# MixerModular_module.net
KiCad netlist of a schematic drawn in EAGLE
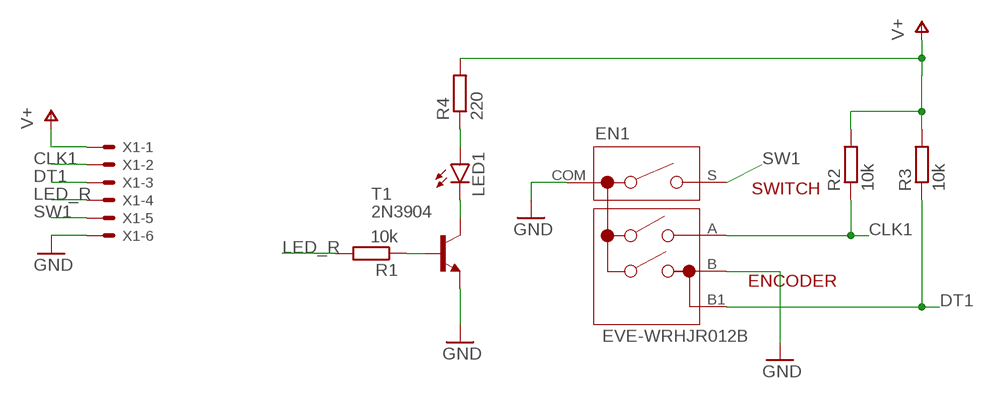
[diagram p0: schematic, sheet 1]

(export (version "E")
  (design (tool "Eeschema 10.0.6"))
  (components
    (comp (ref "EN1")
      (value "EVE-WRHJR012B")
      (footprint "eagle-import:EVE-WRHJR012B")
      (fields
        (field (name "DIGIKEY_PARTNO") "P15917-ND")
        (field (name "MANUFACTURER") "Panasonic Electronic Components")
        (field (name "CREATED_BY") "PCBLayout.com")
      )
      (libsource (lib "eagle-import") (part "EVE-WRHJR012B"))
    )
    (comp (ref "LED1")
      (value "LED5MM")
      (footprint "eagle-import:LED5MM")
      (libsource (lib "eagle-import") (part "LED5MM"))
    )
    (comp (ref "R1")
      (value "10k")
      (footprint "eagle-import:0207_10")
      (libsource (lib "eagle-import") (part "R-EU_0207/10"))
    )
    (comp (ref "R2")
      (value "10k")
      (footprint "eagle-import:0207_10")
      (libsource (lib "eagle-import") (part "R-EU_0207/10"))
    )
    (comp (ref "R3")
      (value "10k")
      (footprint "eagle-import:0207_10")
      (libsource (lib "eagle-import") (part "R-EU_0207/10"))
    )
    (comp (ref "R4")
      (value "220")
      (footprint "eagle-import:0207_10")
      (libsource (lib "eagle-import") (part "R-EU_0207/10"))
    )
    (comp (ref "T1")
      (value "2N3904")
      (footprint "eagle-import:TO92")
      (libsource (lib "eagle-import") (part "2N3904"))
    )
    (comp (ref "X1")
      (value "22-23-2061")
      (footprint "eagle-import:22-23-2061")
      (fields (field (name "MF") "MOLEX"))
      (libsource (lib "eagle-import") (part "22-23-2061"))
    )
  )
  (nets
    (net (code "1") (name "/CLK1") (class "Default")
      (node (ref "EN1") (pin "A") (pinfunction "A_A") (pintype "passive"))
      (node (ref "R2") (pin "1") (pinfunction "1_1") (pintype "passive"))
      (node (ref "X1") (pin "2") (pinfunction "S_2") (pintype "passive"))
    )
    (net (code "2") (name "/DT1") (class "Default")
      (node (ref "EN1") (pin "B1") (pinfunction "B1_B1") (pintype "passive"))
      (node (ref "R3") (pin "1") (pinfunction "1_1") (pintype "passive"))
      (node (ref "X1") (pin "3") (pinfunction "S_3") (pintype "passive"))
    )
    (net (code "3") (name "/LED_R") (class "Default")
      (node (ref "R1") (pin "2") (pinfunction "2_2") (pintype "passive"))
      (node (ref "X1") (pin "4") (pinfunction "S_4") (pintype "passive"))
    )
    (net (code "4") (name "/SW1") (class "Default")
      (node (ref "EN1") (pin "S") (pinfunction "S_S") (pintype "passive"))
      (node (ref "X1") (pin "5") (pinfunction "S_5") (pintype "passive"))
    )
    (net (code "5") (name "GND") (class "Default")
      (node (ref "EN1") (pin "B") (pinfunction "B_B") (pintype "passive"))
      (node (ref "EN1") (pin "COM") (pinfunction "COM_COM") (pintype "passive"))
      (node (ref "T1") (pin "3") (pinfunction "E_3") (pintype "passive"))
      (node (ref "X1") (pin "6") (pinfunction "S_6") (pintype "passive"))
    )
    (net (code "6") (name "Net-(LED1-C)") (class "Default")
      (node (ref "LED1") (pin "K") (pinfunction "C_K") (pintype "passive"))
      (node (ref "T1") (pin "1") (pinfunction "C_1") (pintype "passive"))
    )
    (net (code "7") (name "Net-(LED1-PadA)") (class "Default")
      (node (ref "LED1") (pin "A") (pinfunction "A_A") (pintype "passive"))
      (node (ref "R4") (pin "1") (pinfunction "1_1") (pintype "passive"))
    )
    (net (code "8") (name "Net-(T1-B)") (class "Default")
      (node (ref "R1") (pin "1") (pinfunction "1_1") (pintype "passive"))
      (node (ref "T1") (pin "2") (pinfunction "B_2") (pintype "passive"))
    )
    (net (code "9") (name "V+") (class "Default")
      (node (ref "R2") (pin "2") (pinfunction "2_2") (pintype "passive"))
      (node (ref "R3") (pin "2") (pinfunction "2_2") (pintype "passive"))
      (node (ref "R4") (pin "2") (pinfunction "2_2") (pintype "passive"))
      (node (ref "X1") (pin "1") (pinfunction "S_1") (pintype "passive"))
    )
  )
)
